# datalogger-v11.net
KiCad netlist of a schematic drawn in EAGLE
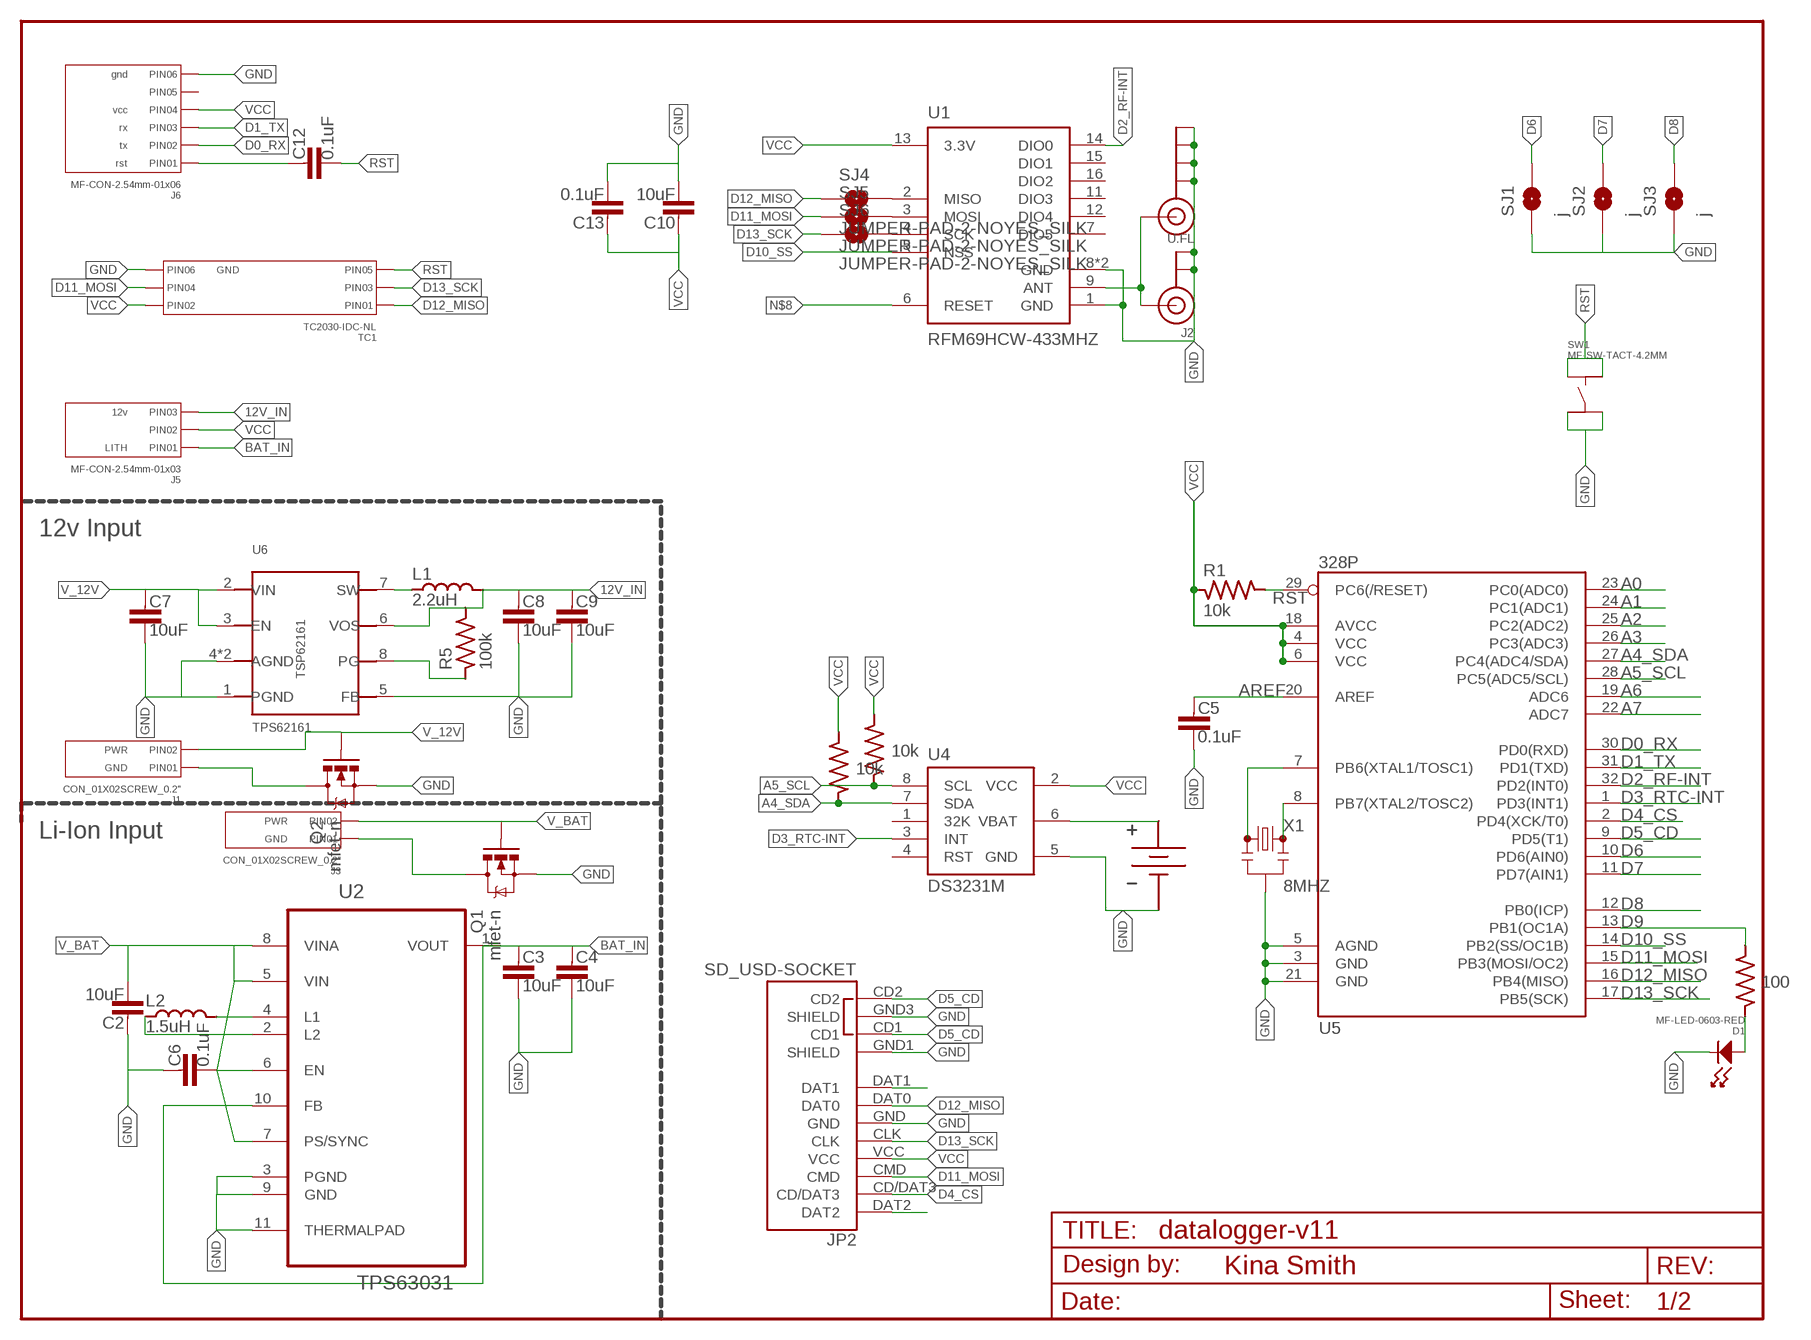
[diagram p0: schematic, sheet 1]
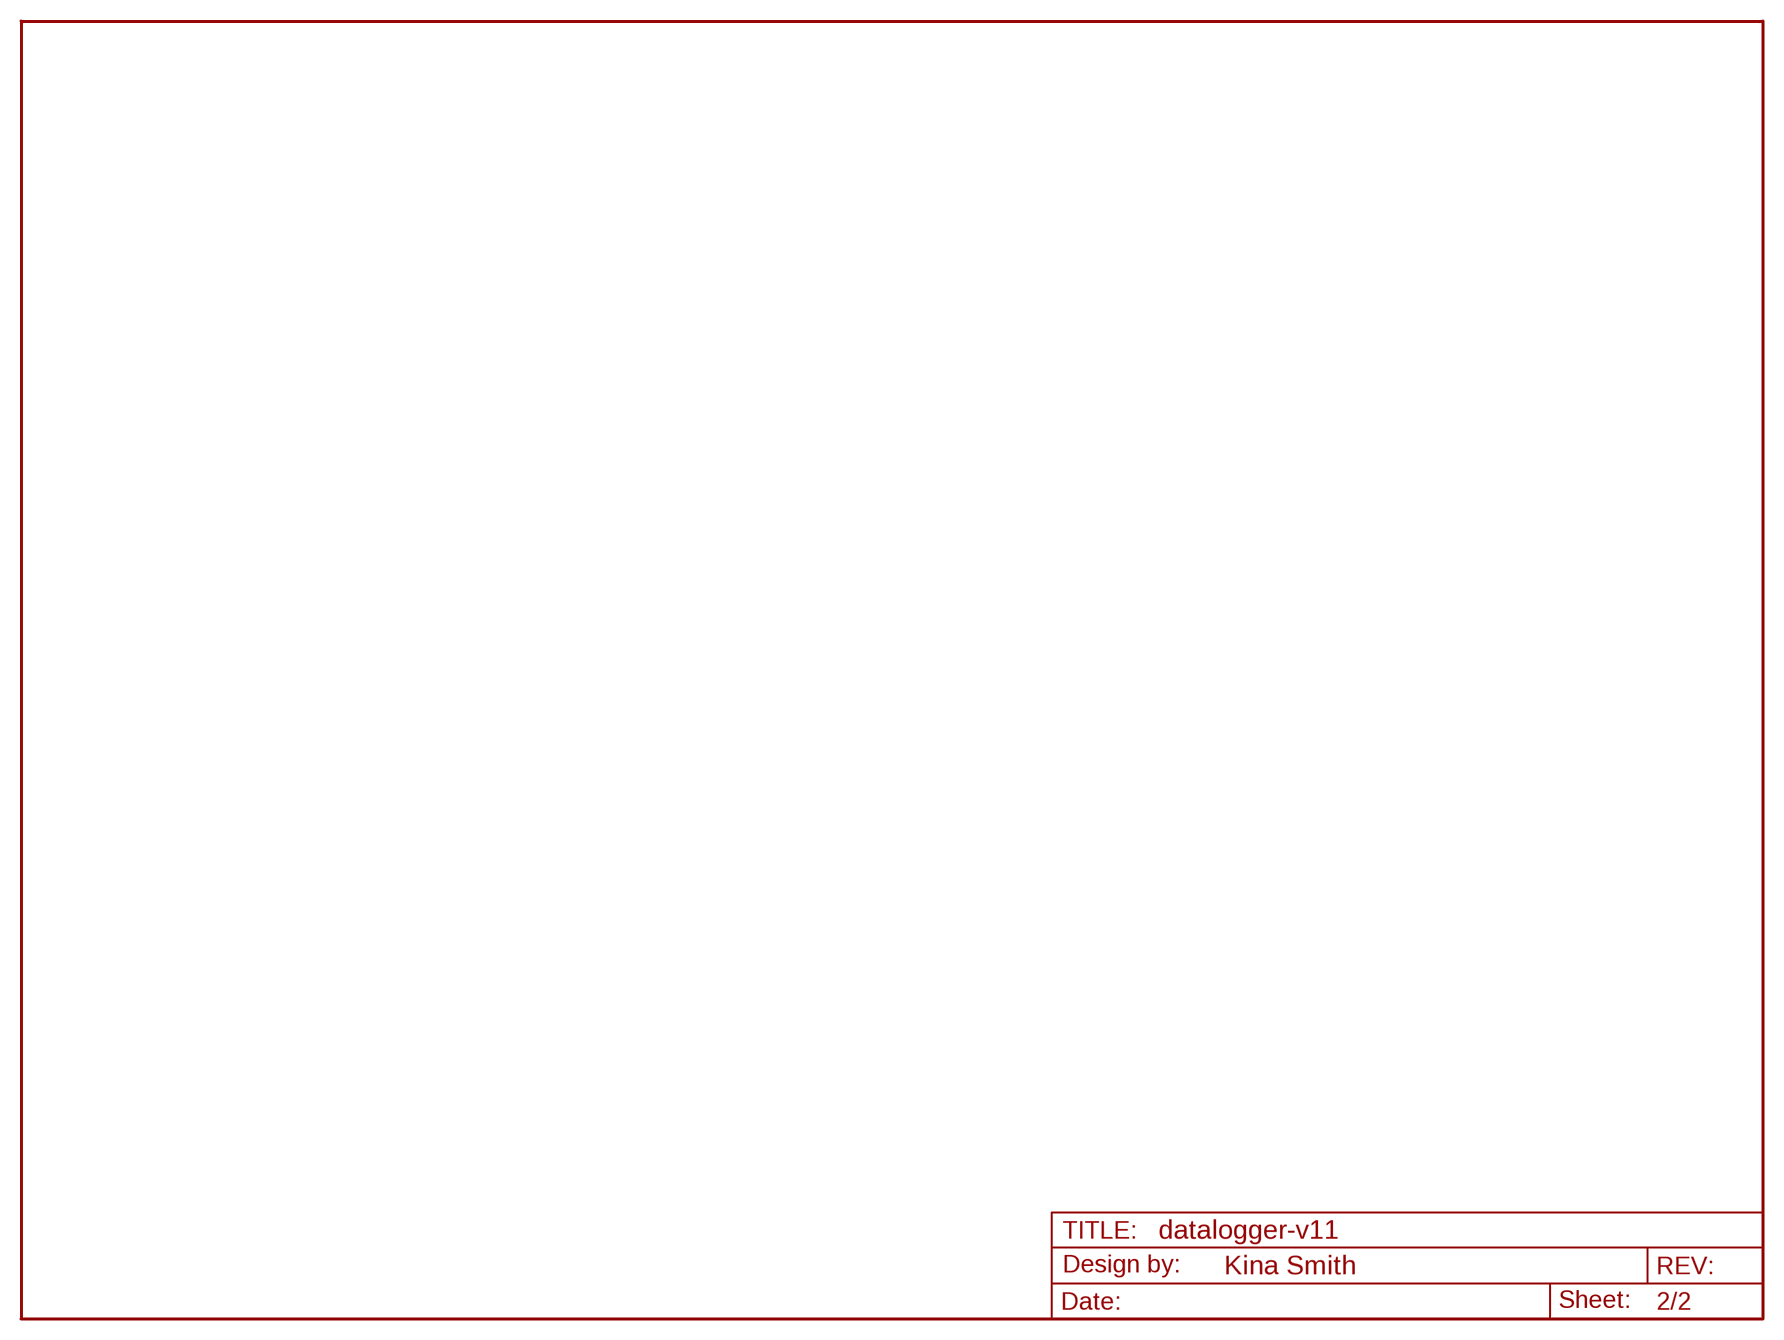
[diagram p1: schematic, sheet 2]

(export (version "E")
  (design (tool "Eeschema 10.0.6"))
  (components
    (comp (ref "FRAME3")
      (value "FRAME-LETTERNO_PACKAGE")
      (footprint "eagle-import:DUMMY")
      (fields (field (name "DESIGNER") "Nobody"))
      (libsource (lib "eagle-import") (part "FRAME-LETTERNO_PACKAGE"))
    )
    (comp (ref "BAT1")
      (value "BATTERY_HOLDER12MM")
      (footprint "eagle-import:BAT_12MM")
      (fields (field (name "PARTNO") "BK-885-TR"))
      (libsource (lib "eagle-import") (part "BATTERY_HOLDER12MM"))
    )
    (comp (ref "C2")
      (value "10uF")
      (footprint "eagle-import:C0805-N")
      (fields (field (name "PARTNO") "GRM21BR61C106KE15L"))
      (libsource (lib "eagle-import") (part "CAPACITOR_NP0805-N"))
    )
    (comp (ref "C3")
      (value "10uF")
      (footprint "eagle-import:C0805-N")
      (fields (field (name "PARTNO") "GRM21BR61C106KE15L"))
      (libsource (lib "eagle-import") (part "CAPACITOR_NP0805-N"))
    )
    (comp (ref "C4")
      (value "10uF")
      (footprint "eagle-import:C0805-N")
      (fields (field (name "PARTNO") "GRM21BR61C106KE15L"))
      (libsource (lib "eagle-import") (part "CAPACITOR_NP0805-N"))
    )
    (comp (ref "C5")
      (value "0.1uF")
      (footprint "eagle-import:C0603-N")
      (fields (field (name "PARTNO") "CC0603KRX7R7BB104"))
      (libsource (lib "eagle-import") (part "CAPACITOR_NP0603-N"))
    )
    (comp (ref "C6")
      (value "0.1uF")
      (footprint "eagle-import:C0603-N")
      (fields (field (name "PARTNO") "CC0603KRX7R7BB104"))
      (libsource (lib "eagle-import") (part "CAPACITOR_NP0603-N"))
    )
    (comp (ref "C7")
      (value "10uF")
      (footprint "eagle-import:C0805-N")
      (fields (field (name "PARTNO") "GRM21BR61C106KE15L"))
      (libsource (lib "eagle-import") (part "CAPACITOR_NP0805-N"))
    )
    (comp (ref "C8")
      (value "10uF")
      (footprint "eagle-import:C0805-N")
      (fields (field (name "PARTNO") "GRM21BR61C106KE15L"))
      (libsource (lib "eagle-import") (part "CAPACITOR_NP0805-N"))
    )
    (comp (ref "C9")
      (value "10uF")
      (footprint "eagle-import:C0805-N")
      (fields (field (name "PARTNO") "GRM21BR61C106KE15L"))
      (libsource (lib "eagle-import") (part "CAPACITOR_NP0805-N"))
    )
    (comp (ref "C10")
      (value "10uF")
      (footprint "eagle-import:C0805-N")
      (fields (field (name "PARTNO") "GRM21BR61C106KE15L"))
      (libsource (lib "eagle-import") (part "CAPACITOR_NP0805-N"))
    )
    (comp (ref "C12")
      (value "0.1uF")
      (footprint "eagle-import:C0603-N")
      (fields (field (name "PARTNO") "CC0603KRX7R7BB104"))
      (libsource (lib "eagle-import") (part "CAPACITOR_NP0603-N"))
    )
    (comp (ref "C13")
      (value "0.1uF")
      (footprint "eagle-import:C0603-N")
      (fields (field (name "PARTNO") "CC0603KRX7R7BB104"))
      (libsource (lib "eagle-import") (part "CAPACITOR_NP0603-N"))
    )
    (comp (ref "D1")
      (value "MF-LED-0603-RED")
      (footprint "eagle-import:LED0603")
      (fields (field (name "HOUSEPART") "YES") (field (name "PARTNO") "LTST-C191KRKT"))
      (libsource (lib "eagle-import") (part "LED_SINGLE-0603-RED"))
    )
    (comp (ref "FRAME1")
      (value "FRAME-LETTERNO_PACKAGE")
      (footprint "eagle-import:DUMMY")
      (fields (field (name "DESIGNER") "Nobody"))
      (libsource (lib "eagle-import") (part "FRAME-LETTERNO_PACKAGE"))
    )
    (comp (ref "J1")
      (value "CON_01X02SCREW_0.2\"")
      (footprint "eagle-import:SCREW_TERM_2POS")
      (fields (field (name "PARTNO") "1729128"))
      (libsource (lib "eagle-import") (part "CON_01X02SCREW_0.2{dblquote}"))
    )
    (comp (ref "J2")
      (value "U.FL")
      (footprint "eagle-import:ADAFRUIT_U.FL")
      (fields (field (name "PARTNO") "U.FL-R-SMT-1(10)"))
      (libsource (lib "eagle-import") (part "ANTENNA_U.FL"))
    )
    (comp (ref "J3")
      (value "CON_01X02SCREW_0.2\"")
      (footprint "eagle-import:SCREW_TERM_2POS")
      (fields (field (name "PARTNO") "1729128"))
      (libsource (lib "eagle-import") (part "CON_01X02SCREW_0.2{dblquote}"))
    )
    (comp (ref "J4")
      (value "ANTENNA_SMA_EDGE")
      (footprint "eagle-import:SMA-EDGE")
      (fields (field (name "PARTNO") "EMPCB.SMAFSTJ.B.HT"))
      (libsource (lib "eagle-import") (part "ANTENNA_SMA_EDGE"))
    )
    (comp (ref "J5")
      (value "MF-CON-2.54mm-01x03")
      (footprint "eagle-import:PTH_2.54MM_01X03")
      (fields
        (field (name "HOUSEPART") "YES")
        (field (name "LABEL01") "LITH")
        (field (name "LABEL03") "12v")
        (field (name "PARTNO") "NA")
      )
      (libsource (lib "eagle-import") (part "CON_01X03_PTH_2.54MM"))
    )
    (comp (ref "J6")
      (value "MF-CON-2.54mm-01x06")
      (footprint "eagle-import:PTH_2.54MM_01X06")
      (fields
        (field (name "HOUSEPART") "YES")
        (field (name "LABEL01") "rst")
        (field (name "LABEL02") "tx")
        (field (name "LABEL03") "rx")
        (field (name "LABEL04") "vcc")
        (field (name "LABEL06") "gnd")
        (field (name "PARTNO") "NA")
      )
      (libsource (lib "eagle-import") (part "CON_01X06_PTH_2.54MM"))
    )
    (comp (ref "JP2")
      (value "SD_USD-SOCKET")
      (footprint "eagle-import:MICRO-SD-SOCKET-SDIO")
      (fields (field (name "PARTNO") "101-00660-68-6"))
      (libsource (lib "eagle-import") (part "SD_USD-SOCKET"))
    )
    (comp (ref "L1")
      (value "2.2uH")
      (footprint "eagle-import:L2520")
      (fields (field (name "PARTNO") "VLS252012T-2R2M1R3 "))
      (libsource (lib "eagle-import") (part "INDUCTOR2520"))
    )
    (comp (ref "L2")
      (value "1.5uH")
      (footprint "eagle-import:L3030")
      (fields (field (name "PARTNO") "NR3015T1R5N"))
      (libsource (lib "eagle-import") (part "INDUCTOR3030"))
    )
    (comp (ref "Q1")
      (value "mfet-n")
      (footprint "eagle-import:SOT23-3")
      (fields (field (name "PARTNO") "SI2312BDS-T1-GE3"))
      (libsource (lib "eagle-import") (part "MOSFET-NCHANNELSOT23-3"))
    )
    (comp (ref "Q2")
      (value "mfet-n")
      (footprint "eagle-import:SOT23-3")
      (fields (field (name "PARTNO") "SI2312BDS-T1-GE3"))
      (libsource (lib "eagle-import") (part "MOSFET-NCHANNELSOT23-3"))
    )
    (comp (ref "R1")
      (value "10k")
      (footprint "eagle-import:R0603-N")
      (fields (field (name "PARTNO") "RC0603FR-0710KL"))
      (libsource (lib "eagle-import") (part "RESISTOR0603-N"))
    )
    (comp (ref "R2")
      (value "100")
      (footprint "eagle-import:R0603-N")
      (fields (field (name "PARTNO") "RC0603FR-07100RL"))
      (libsource (lib "eagle-import") (part "RESISTOR0603-N"))
    )
    (comp (ref "R3")
      (value "10k")
      (footprint "eagle-import:R0603-N")
      (fields (field (name "PARTNO") "RC0603FR-0710KL"))
      (libsource (lib "eagle-import") (part "RESISTOR0603-N"))
    )
    (comp (ref "R4")
      (value "10k")
      (footprint "eagle-import:R0603-N")
      (fields (field (name "PARTNO") "RC0603FR-0710KL"))
      (libsource (lib "eagle-import") (part "RESISTOR0603-N"))
    )
    (comp (ref "R5")
      (value "100k")
      (footprint "eagle-import:R0603-N")
      (fields (field (name "PARTNO") "RC0603FR-07100KL"))
      (libsource (lib "eagle-import") (part "RESISTOR0603-N"))
    )
    (comp (ref "SJ1")
      (value "j")
      (footprint "eagle-import:PAD-JUMPER-2-NO_YES_SILK")
      (fields (field (name "PARTNO") "NA"))
      (libsource (lib "eagle-import") (part "JUMPER-PAD-2-NOYES_SILK"))
    )
    (comp (ref "SJ2")
      (value "j")
      (footprint "eagle-import:PAD-JUMPER-2-NO_YES_SILK")
      (fields (field (name "PARTNO") "NA"))
      (libsource (lib "eagle-import") (part "JUMPER-PAD-2-NOYES_SILK"))
    )
    (comp (ref "SJ3")
      (value "j")
      (footprint "eagle-import:PAD-JUMPER-2-NO_YES_SILK")
      (fields (field (name "PARTNO") "NA"))
      (libsource (lib "eagle-import") (part "JUMPER-PAD-2-NOYES_SILK"))
    )
    (comp (ref "SJ4")
      (value "JUMPER-PAD-2-NOYES_SILK")
      (footprint "eagle-import:PAD-JUMPER-2-NO_YES_SILK")
      (fields (field (name "PARTNO") "NA"))
      (libsource (lib "eagle-import") (part "JUMPER-PAD-2-NOYES_SILK"))
    )
    (comp (ref "SJ5")
      (value "JUMPER-PAD-2-NOYES_SILK")
      (footprint "eagle-import:PAD-JUMPER-2-NO_YES_SILK")
      (fields (field (name "PARTNO") "NA"))
      (libsource (lib "eagle-import") (part "JUMPER-PAD-2-NOYES_SILK"))
    )
    (comp (ref "SJ6")
      (value "JUMPER-PAD-2-NOYES_SILK")
      (footprint "eagle-import:PAD-JUMPER-2-NO_YES_SILK")
      (fields (field (name "PARTNO") "NA"))
      (libsource (lib "eagle-import") (part "JUMPER-PAD-2-NOYES_SILK"))
    )
    (comp (ref "SW1")
      (value "MF-SW-TACT-4.2MM")
      (footprint "eagle-import:TACT4.2MM")
      (fields (field (name "HOUSEPART") "YES") (field (name "PARTNO") "PTS810 SJM 250 SMTR LFS"))
      (libsource (lib "eagle-import") (part "TACT_4.2MM"))
    )
    (comp (ref "TC1")
      (value "TC2030-IDC-NL")
      (footprint "eagle-import:TC2030-IDC-NL")
      (fields (field (name "HOUSEPART") "NO") (field (name "PARTNO") "NA"))
      (libsource (lib "eagle-import") (part "CON_02X03_TC2030-IDC-NL_AVRISP"))
    )
    (comp (ref "U1")
      (value "RFM69HCW-433MHZ")
      (footprint "eagle-import:RFM69HCW-XXXS2")
      (fields (field (name "PARTNO") "COM-13910"))
      (libsource (lib "eagle-import") (part "RFM69HCW-433MHZ"))
    )
    (comp (ref "U2")
      (value "TPS63031")
      (footprint "eagle-import:SON50P260X260X80-11N")
      (fields (field (name "MPN") "TPS63031DSK") (field (name "PARTNO") "TPS63031DSKR"))
      (libsource (lib "eagle-import") (part "TPS63031"))
    )
    (comp (ref "U4")
      (value "DS3231M")
      (footprint "eagle-import:SO08")
      (fields (field (name "PARTNO") "DS3231MZ/V+"))
      (libsource (lib "eagle-import") (part "DS3231M"))
    )
    (comp (ref "U5")
      (value "328P")
      (footprint "eagle-import:TQFP32-08")
      (fields (field (name "PARTNO") "ATMEGA328P-AU"))
      (libsource (lib "eagle-import") (part "ATMEGA328P-AU"))
    )
    (comp (ref "U6")
      (value "TPS62161")
      (footprint "eagle-import:WSON-8")
      (fields (field (name "PARTNO") "TPS62161DSGR"))
      (libsource (lib "eagle-import") (part "TPS62161"))
    )
    (comp (ref "X1")
      (value "8MHZ")
      (footprint "eagle-import:RESONATOR-SMD")
      (fields (field (name "PARTNO") "CSTCE8M00G55-R0"))
      (libsource (lib "eagle-import") (part "RESONATOR8MHZ"))
    )
  )
  (nets
    (net (code "1") (name "12V_IN") (class "Default")
      (node (ref "C8") (pin "1") (pinfunction "1_1") (pintype "passive"))
      (node (ref "C9") (pin "1") (pinfunction "1_1") (pintype "passive"))
      (node (ref "J5") (pin "P$3") (pinfunction "PIN3_P$3") (pintype "bidirectional"))
      (node (ref "L1") (pin "P$2") (pinfunction "P$2_P$2") (pintype "passive"))
      (node (ref "R5") (pin "2") (pinfunction "P$2_2") (pintype "passive"))
      (node (ref "U6") (pin "6") (pinfunction "VOS_6") (pintype "bidirectional"))
    )
    (net (code "2") (name "A0") (class "Default")
      (node (ref "U5") (pin "23") (pinfunction "PC0(ADC0)_23") (pintype "bidirectional"))
    )
    (net (code "3") (name "A1") (class "Default")
      (node (ref "U5") (pin "24") (pinfunction "PC1(ADC1)_24") (pintype "bidirectional"))
    )
    (net (code "4") (name "A2") (class "Default")
      (node (ref "U5") (pin "25") (pinfunction "PC2(ADC2)_25") (pintype "bidirectional"))
    )
    (net (code "5") (name "A3") (class "Default")
      (node (ref "U5") (pin "26") (pinfunction "PC3(ADC3)_26") (pintype "bidirectional"))
    )
    (net (code "6") (name "A4_SDA") (class "Default")
      (node (ref "R4") (pin "1") (pinfunction "P$1_1") (pintype "passive"))
      (node (ref "U4") (pin "7") (pinfunction "SDA_7") (pintype "bidirectional"))
      (node (ref "U5") (pin "27") (pinfunction "PC4(ADC4/SDA)_27") (pintype "bidirectional"))
    )
    (net (code "7") (name "A5_SCL") (class "Default")
      (node (ref "R3") (pin "1") (pinfunction "P$1_1") (pintype "passive"))
      (node (ref "U4") (pin "8") (pinfunction "SCL_8") (pintype "bidirectional"))
      (node (ref "U5") (pin "28") (pinfunction "PC5(ADC5/SCL)_28") (pintype "bidirectional"))
    )
    (net (code "8") (name "A6") (class "Default")
      (node (ref "U5") (pin "19") (pinfunction "ADC6_19") (pintype "bidirectional"))
    )
    (net (code "9") (name "A7") (class "Default")
      (node (ref "U5") (pin "22") (pinfunction "ADC7_22") (pintype "bidirectional"))
    )
    (net (code "10") (name "AREF") (class "Default")
      (node (ref "C5") (pin "1") (pinfunction "1_1") (pintype "passive"))
      (node (ref "U5") (pin "20") (pinfunction "AREF_20") (pintype "bidirectional"))
    )
    (net (code "11") (name "BAT_IN") (class "Default")
      (node (ref "C3") (pin "1") (pinfunction "1_1") (pintype "passive"))
      (node (ref "C4") (pin "1") (pinfunction "1_1") (pintype "passive"))
      (node (ref "J5") (pin "P$1") (pinfunction "PIN1_P$1") (pintype "bidirectional"))
      (node (ref "U2") (pin "1") (pinfunction "VOUT_1") (pintype "output"))
      (node (ref "U2") (pin "10") (pinfunction "FB_10") (pintype "input"))
    )
    (net (code "12") (name "D0_RX") (class "Default")
      (node (ref "J6") (pin "P$2") (pinfunction "PIN2_P$2") (pintype "bidirectional"))
      (node (ref "U5") (pin "30") (pinfunction "PD0(RXD)_30") (pintype "bidirectional"))
    )
    (net (code "13") (name "D1_TX") (class "Default")
      (node (ref "J6") (pin "P$3") (pinfunction "PIN3_P$3") (pintype "bidirectional"))
      (node (ref "U5") (pin "31") (pinfunction "PD1(TXD)_31") (pintype "bidirectional"))
    )
    (net (code "14") (name "D2_RF-INT") (class "Default")
      (node (ref "U1") (pin "14") (pinfunction "DIO0_14") (pintype "bidirectional"))
      (node (ref "U5") (pin "32") (pinfunction "PD2(INT0)_32") (pintype "bidirectional"))
    )
    (net (code "15") (name "D3_RTC-INT") (class "Default")
      (node (ref "U4") (pin "3") (pinfunction "INT_3") (pintype "bidirectional"))
      (node (ref "U5") (pin "1") (pinfunction "PD3(INT1)_1") (pintype "bidirectional"))
    )
    (net (code "16") (name "D4_CS") (class "Default")
      (node (ref "JP2") (pin "CD/DAT3") (pinfunction "CD/DAT3_CD/DAT3") (pintype "bidirectional"))
      (node (ref "U5") (pin "2") (pinfunction "PD4(XCK/T0)_2") (pintype "bidirectional"))
    )
    (net (code "17") (name "D5_CD") (class "Default")
      (node (ref "JP2") (pin "CD1") (pinfunction "CD1_CD1") (pintype "bidirectional"))
      (node (ref "JP2") (pin "CD2") (pinfunction "CD2_CD2") (pintype "bidirectional"))
      (node (ref "U5") (pin "9") (pinfunction "PD5(T1)_9") (pintype "bidirectional"))
    )
    (net (code "18") (name "D6") (class "Default")
      (node (ref "SJ1") (pin "2") (pinfunction "2_2") (pintype "passive"))
      (node (ref "U5") (pin "10") (pinfunction "PD6(AIN0)_10") (pintype "bidirectional"))
    )
    (net (code "19") (name "D7") (class "Default")
      (node (ref "SJ2") (pin "2") (pinfunction "2_2") (pintype "passive"))
      (node (ref "U5") (pin "11") (pinfunction "PD7(AIN1)_11") (pintype "bidirectional"))
    )
    (net (code "20") (name "D8") (class "Default")
      (node (ref "SJ3") (pin "2") (pinfunction "2_2") (pintype "passive"))
      (node (ref "U5") (pin "12") (pinfunction "PB0(ICP)_12") (pintype "bidirectional"))
    )
    (net (code "21") (name "D9") (class "Default")
      (node (ref "R2") (pin "2") (pinfunction "P$2_2") (pintype "passive"))
      (node (ref "U5") (pin "13") (pinfunction "PB1(OC1A)_13") (pintype "bidirectional"))
    )
    (net (code "22") (name "D10_SS") (class "Default")
      (node (ref "U1") (pin "5") (pinfunction "NSS_5") (pintype "input"))
      (node (ref "U5") (pin "14") (pinfunction "PB2(SS/OC1B)_14") (pintype "bidirectional"))
    )
    (net (code "23") (name "D11_MOSI") (class "Default")
      (node (ref "JP2") (pin "CMD") (pinfunction "CMD_CMD") (pintype "bidirectional"))
      (node (ref "SJ5") (pin "1") (pinfunction "1_1") (pintype "passive"))
      (node (ref "TC1") (pin "P$4") (pinfunction "PIN4_P$4") (pintype "bidirectional"))
      (node (ref "U5") (pin "15") (pinfunction "PB3(MOSI/OC2)_15") (pintype "bidirectional"))
    )
    (net (code "24") (name "D12_MISO") (class "Default")
      (node (ref "JP2") (pin "DAT0") (pinfunction "DAT0_DAT0") (pintype "bidirectional"))
      (node (ref "SJ4") (pin "1") (pinfunction "1_1") (pintype "passive"))
      (node (ref "TC1") (pin "P$1") (pinfunction "PIN1_P$1") (pintype "bidirectional"))
      (node (ref "U5") (pin "16") (pinfunction "PB4(MISO)_16") (pintype "bidirectional"))
    )
    (net (code "25") (name "D13_SCK") (class "Default")
      (node (ref "JP2") (pin "CLK") (pinfunction "CLK_CLK") (pintype "bidirectional"))
      (node (ref "SJ6") (pin "1") (pinfunction "1_1") (pintype "passive"))
      (node (ref "TC1") (pin "P$3") (pinfunction "PIN3_P$3") (pintype "bidirectional"))
      (node (ref "U5") (pin "17") (pinfunction "PB5(SCK)_17") (pintype "bidirectional"))
    )
    (net (code "26") (name "GND") (class "Default")
      (node (ref "BAT1") (pin "GND") (pinfunction "GND_GND") (pintype "bidirectional"))
      (node (ref "C10") (pin "2") (pinfunction "2_2") (pintype "passive"))
      (node (ref "C13") (pin "2") (pinfunction "2_2") (pintype "passive"))
      (node (ref "C2") (pin "1") (pinfunction "1_1") (pintype "passive"))
      (node (ref "C3") (pin "2") (pinfunction "2_2") (pintype "passive"))
      (node (ref "C4") (pin "2") (pinfunction "2_2") (pintype "passive"))
      (node (ref "C5") (pin "2") (pinfunction "2_2") (pintype "passive"))
      (node (ref "C6") (pin "1") (pinfunction "1_1") (pintype "passive"))
      (node (ref "C7") (pin "2") (pinfunction "2_2") (pintype "passive"))
      (node (ref "C8") (pin "2") (pinfunction "2_2") (pintype "passive"))
      (node (ref "C9") (pin "2") (pinfunction "2_2") (pintype "passive"))
      (node (ref "D1") (pin "CATHODE") (pinfunction "CATHODE_CATHODE") (pintype "power_in"))
      (node (ref "J2") (pin "1") (pinfunction "GND_1") (pintype "passive"))
      (node (ref "J2") (pin "2") (pinfunction "GND_2") (pintype "passive"))
      (node (ref "J4") (pin "GND@0") (pinfunction "GND_GND@0") (pintype "bidirectional"))
      (node (ref "J4") (pin "GND@1") (pinfunction "GND_GND@1") (pintype "bidirectional"))
      (node (ref "J4") (pin "GND@2") (pinfunction "GND_GND@2") (pintype "bidirectional"))
      (node (ref "J4") (pin "GND@3") (pinfunction "GND_GND@3") (pintype "bidirectional"))
      (node (ref "J6") (pin "P$6") (pinfunction "PIN6_P$6") (pintype "bidirectional"))
      (node (ref "JP2") (pin "GND") (pinfunction "GND_GND") (pintype "bidirectional"))
      (node (ref "JP2") (pin "GND1") (pinfunction "SHIELD_GND1") (pintype "bidirectional"))
      (node (ref "JP2") (pin "GND3") (pinfunction "SHIELD_GND3") (pintype "bidirectional"))
      (node (ref "Q1") (pin "2") (pinfunction "S_2") (pintype "passive"))
      (node (ref "Q2") (pin "2") (pinfunction "S_2") (pintype "passive"))
      (node (ref "SJ1") (pin "1") (pinfunction "1_1") (pintype "passive"))
      (node (ref "SJ2") (pin "1") (pinfunction "1_1") (pintype "passive"))
      (node (ref "SJ3") (pin "1") (pinfunction "1_1") (pintype "passive"))
      (node (ref "SW1") (pin "P$3") (pinfunction "P$3_P$3") (pintype "bidirectional"))
      (node (ref "SW1") (pin "P$4") (pinfunction "P$4_P$4") (pintype "bidirectional"))
      (node (ref "TC1") (pin "P$6") (pinfunction "PIN6_P$6") (pintype "bidirectional"))
      (node (ref "U1") (pin "1") (pinfunction "GND_1") (pintype "power_in"))
      (node (ref "U1") (pin "10") (pinfunction "GND_10") (pintype "power_in"))
      (node (ref "U1") (pin "8") (pinfunction "GND_8") (pintype "power_in"))
      (node (ref "U2") (pin "11") (pinfunction "THERMALPAD_11") (pintype "passive"))
      (node (ref "U2") (pin "3") (pinfunction "PGND_3") (pintype "passive"))
      (node (ref "U2") (pin "9") (pinfunction "GND_9") (pintype "passive"))
      (node (ref "U4") (pin "5") (pinfunction "GND_5") (pintype "power_in"))
      (node (ref "U5") (pin "21") (pinfunction "GND_21") (pintype "bidirectional"))
      (node (ref "U5") (pin "3") (pinfunction "GND_3") (pintype "bidirectional"))
      (node (ref "U5") (pin "5") (pinfunction "AGND_5") (pintype "bidirectional"))
      (node (ref "U6") (pin "1") (pinfunction "PGND_1") (pintype "bidirectional"))
      (node (ref "U6") (pin "4") (pinfunction "AGND_4") (pintype "bidirectional"))
      (node (ref "U6") (pin "5") (pinfunction "FB_5") (pintype "bidirectional"))
      (node (ref "U6") (pin "P$9") (pinfunction "AGND_P$9") (pintype "bidirectional"))
      (node (ref "X1") (pin "2") (pinfunction "2_2") (pintype "passive"))
    )
    (net (code "27") (name "N$8") (class "Default")
      (node (ref "U1") (pin "6") (pinfunction "RESET_6") (pintype "input"))
    )
    (net (code "28") (name "Net-(J1-PIN1)") (class "Default")
      (node (ref "J1") (pin "GND") (pinfunction "PIN1_GND") (pintype "bidirectional"))
      (node (ref "Q2") (pin "3") (pinfunction "D_3") (pintype "passive"))
    )
    (net (code "29") (name "Net-(J2-SIGNAL)") (class "Default")
      (node (ref "J2") (pin "3") (pinfunction "SIGNAL_3") (pintype "passive"))
      (node (ref "J4") (pin "SIG") (pinfunction "SIGNAL_SIG") (pintype "bidirectional"))
      (node (ref "U1") (pin "9") (pinfunction "ANT_9") (pintype "passive"))
    )
    (net (code "30") (name "Net-(J3-PIN1)") (class "Default")
      (node (ref "J3") (pin "GND") (pinfunction "PIN1_GND") (pintype "bidirectional"))
      (node (ref "Q1") (pin "3") (pinfunction "D_3") (pintype "passive"))
    )
    (net (code "31") (name "Net-(J6-PIN1)") (class "Default")
      (node (ref "C12") (pin "1") (pinfunction "1_1") (pintype "passive"))
      (node (ref "J6") (pin "P$1") (pinfunction "PIN1_P$1") (pintype "bidirectional"))
    )
    (net (code "32") (name "Net-(R2-P$1)") (class "Default")
      (node (ref "D1") (pin "ANODE") (pinfunction "ANODE_ANODE") (pintype "power_in"))
      (node (ref "R2") (pin "1") (pinfunction "P$1_1") (pintype "passive"))
    )
    (net (code "33") (name "Net-(R5-P$1)") (class "Default")
      (node (ref "R5") (pin "1") (pinfunction "P$1_1") (pintype "passive"))
      (node (ref "U6") (pin "8") (pinfunction "PG_8") (pintype "bidirectional"))
    )
    (net (code "34") (name "Net-(U1-MISO)") (class "Default")
      (node (ref "SJ4") (pin "2") (pinfunction "2_2") (pintype "passive"))
      (node (ref "U1") (pin "2") (pinfunction "MISO_2") (pintype "bidirectional"))
    )
    (net (code "35") (name "Net-(U1-MOSI)") (class "Default")
      (node (ref "SJ5") (pin "2") (pinfunction "2_2") (pintype "passive"))
      (node (ref "U1") (pin "3") (pinfunction "MOSI_3") (pintype "input"))
    )
    (net (code "36") (name "Net-(U1-SCK)") (class "Default")
      (node (ref "SJ6") (pin "2") (pinfunction "2_2") (pintype "passive"))
      (node (ref "U1") (pin "4") (pinfunction "SCK_4") (pintype "input"))
    )
    (net (code "37") (name "Net-(U2-L1)") (class "Default")
      (node (ref "L2") (pin "P$2") (pinfunction "P$2_P$2") (pintype "passive"))
      (node (ref "U2") (pin "4") (pinfunction "L1_4") (pintype "input"))
    )
    (net (code "38") (name "Net-(U2-L2)") (class "Default")
      (node (ref "L2") (pin "P$1") (pinfunction "P$1_P$1") (pintype "passive"))
      (node (ref "U2") (pin "2") (pinfunction "L2_2") (pintype "input"))
    )
    (net (code "39") (name "Net-(U4-VBAT)") (class "Default")
      (node (ref "BAT1") (pin "PWR@1") (pinfunction "VBAT_PWR@1") (pintype "bidirectional"))
      (node (ref "BAT1") (pin "PWR@2") (pinfunction "VBAT_PWR@2") (pintype "bidirectional"))
      (node (ref "U4") (pin "6") (pinfunction "VBAT_6") (pintype "power_in"))
    )
    (net (code "40") (name "Net-(U5-PB6(XTAL1{slash}TOSC1))") (class "Default")
      (node (ref "U5") (pin "7") (pinfunction "PB6(XTAL1/TOSC1)_7") (pintype "bidirectional"))
      (node (ref "X1") (pin "1") (pinfunction "1_1") (pintype "passive"))
    )
    (net (code "41") (name "Net-(U5-PB7(XTAL2{slash}TOSC2))") (class "Default")
      (node (ref "U5") (pin "8") (pinfunction "PB7(XTAL2/TOSC2)_8") (pintype "bidirectional"))
      (node (ref "X1") (pin "3") (pinfunction "3_3") (pintype "passive"))
    )
    (net (code "42") (name "Net-(U6-SW)") (class "Default")
      (node (ref "L1") (pin "P$1") (pinfunction "P$1_P$1") (pintype "passive"))
      (node (ref "U6") (pin "7") (pinfunction "SW_7") (pintype "bidirectional"))
    )
    (net (code "43") (name "RST") (class "Default")
      (node (ref "C12") (pin "2") (pinfunction "2_2") (pintype "passive"))
      (node (ref "R1") (pin "2") (pinfunction "P$2_2") (pintype "passive"))
      (node (ref "SW1") (pin "P$1") (pinfunction "P$1_P$1") (pintype "bidirectional"))
      (node (ref "SW1") (pin "P$2") (pinfunction "P$2_P$2") (pintype "bidirectional"))
      (node (ref "TC1") (pin "P$5") (pinfunction "PIN5_P$5") (pintype "bidirectional"))
      (node (ref "U5") (pin "29") (pinfunction "PC6(/RESET)_29") (pintype "bidirectional"))
    )
    (net (code "44") (name "VCC") (class "Default")
      (node (ref "C10") (pin "1") (pinfunction "1_1") (pintype "passive"))
      (node (ref "C13") (pin "1") (pinfunction "1_1") (pintype "passive"))
      (node (ref "J5") (pin "P$2") (pinfunction "PIN2_P$2") (pintype "bidirectional"))
      (node (ref "J6") (pin "P$4") (pinfunction "PIN4_P$4") (pintype "bidirectional"))
      (node (ref "JP2") (pin "VCC") (pinfunction "VCC_VCC") (pintype "bidirectional"))
      (node (ref "R1") (pin "1") (pinfunction "P$1_1") (pintype "passive"))
      (node (ref "R3") (pin "2") (pinfunction "P$2_2") (pintype "passive"))
      (node (ref "R4") (pin "2") (pinfunction "P$2_2") (pintype "passive"))
      (node (ref "TC1") (pin "P$2") (pinfunction "PIN2_P$2") (pintype "bidirectional"))
      (node (ref "U1") (pin "13") (pinfunction "3.3V_13") (pintype "power_in"))
      (node (ref "U4") (pin "2") (pinfunction "VCC_2") (pintype "power_in"))
      (node (ref "U5") (pin "18") (pinfunction "AVCC_18") (pintype "bidirectional"))
      (node (ref "U5") (pin "4") (pinfunction "VCC_4") (pintype "bidirectional"))
      (node (ref "U5") (pin "6") (pinfunction "VCC_6") (pintype "bidirectional"))
    )
    (net (code "45") (name "V_12V") (class "Default")
      (node (ref "C7") (pin "1") (pinfunction "1_1") (pintype "passive"))
      (node (ref "J1") (pin "PWR") (pinfunction "PIN2_PWR") (pintype "bidirectional"))
      (node (ref "Q2") (pin "1") (pinfunction "G_1") (pintype "passive"))
      (node (ref "U6") (pin "2") (pinfunction "VIN_2") (pintype "bidirectional"))
      (node (ref "U6") (pin "3") (pinfunction "EN_3") (pintype "bidirectional"))
    )
    (net (code "46") (name "V_BAT") (class "Default")
      (node (ref "C2") (pin "2") (pinfunction "2_2") (pintype "passive"))
      (node (ref "C6") (pin "2") (pinfunction "2_2") (pintype "passive"))
      (node (ref "J3") (pin "PWR") (pinfunction "PIN2_PWR") (pintype "bidirectional"))
      (node (ref "Q1") (pin "1") (pinfunction "G_1") (pintype "passive"))
      (node (ref "U2") (pin "5") (pinfunction "VIN_5") (pintype "input"))
      (node (ref "U2") (pin "6") (pinfunction "EN_6") (pintype "input"))
      (node (ref "U2") (pin "7") (pinfunction "PS/SYNC_7") (pintype "input"))
      (node (ref "U2") (pin "8") (pinfunction "VINA_8") (pintype "input"))
    )
    (net (code "47") (name "unconnected-(J6-PIN5-PadP$5)") (class "Default")
      (node (ref "J6") (pin "P$5") (pinfunction "PIN5_P$5") (pintype "bidirectional"))
    )
    (net (code "48") (name "unconnected-(JP2-PadDAT1)") (class "Default")
      (node (ref "JP2") (pin "DAT1") (pinfunction "DAT1_DAT1") (pintype "bidirectional"))
    )
    (net (code "49") (name "unconnected-(JP2-PadDAT2)") (class "Default")
      (node (ref "JP2") (pin "DAT2") (pinfunction "DAT2_DAT2") (pintype "bidirectional"))
    )
    (net (code "50") (name "unconnected-(U1-DIO1-Pad15)") (class "Default")
      (node (ref "U1") (pin "15") (pinfunction "DIO1_15") (pintype "bidirectional"))
    )
    (net (code "51") (name "unconnected-(U1-DIO2-Pad16)") (class "Default")
      (node (ref "U1") (pin "16") (pinfunction "DIO2_16") (pintype "bidirectional"))
    )
    (net (code "52") (name "unconnected-(U1-DIO3-Pad11)") (class "Default")
      (node (ref "U1") (pin "11") (pinfunction "DIO3_11") (pintype "bidirectional"))
    )
    (net (code "53") (name "unconnected-(U1-DIO4-Pad12)") (class "Default")
      (node (ref "U1") (pin "12") (pinfunction "DIO4_12") (pintype "bidirectional"))
    )
    (net (code "54") (name "unconnected-(U1-DIO5-Pad7)") (class "Default")
      (node (ref "U1") (pin "7") (pinfunction "DIO5_7") (pintype "bidirectional"))
    )
    (net (code "55") (name "unconnected-(U4-32K-Pad1)") (class "Default")
      (node (ref "U4") (pin "1") (pinfunction "32K_1") (pintype "bidirectional"))
    )
    (net (code "56") (name "unconnected-(U4-RST-Pad4)") (class "Default")
      (node (ref "U4") (pin "4") (pinfunction "RST_4") (pintype "bidirectional"))
    )
  )
)
